# 4x_board.net
KiCad netlist of a schematic drawn in EAGLE
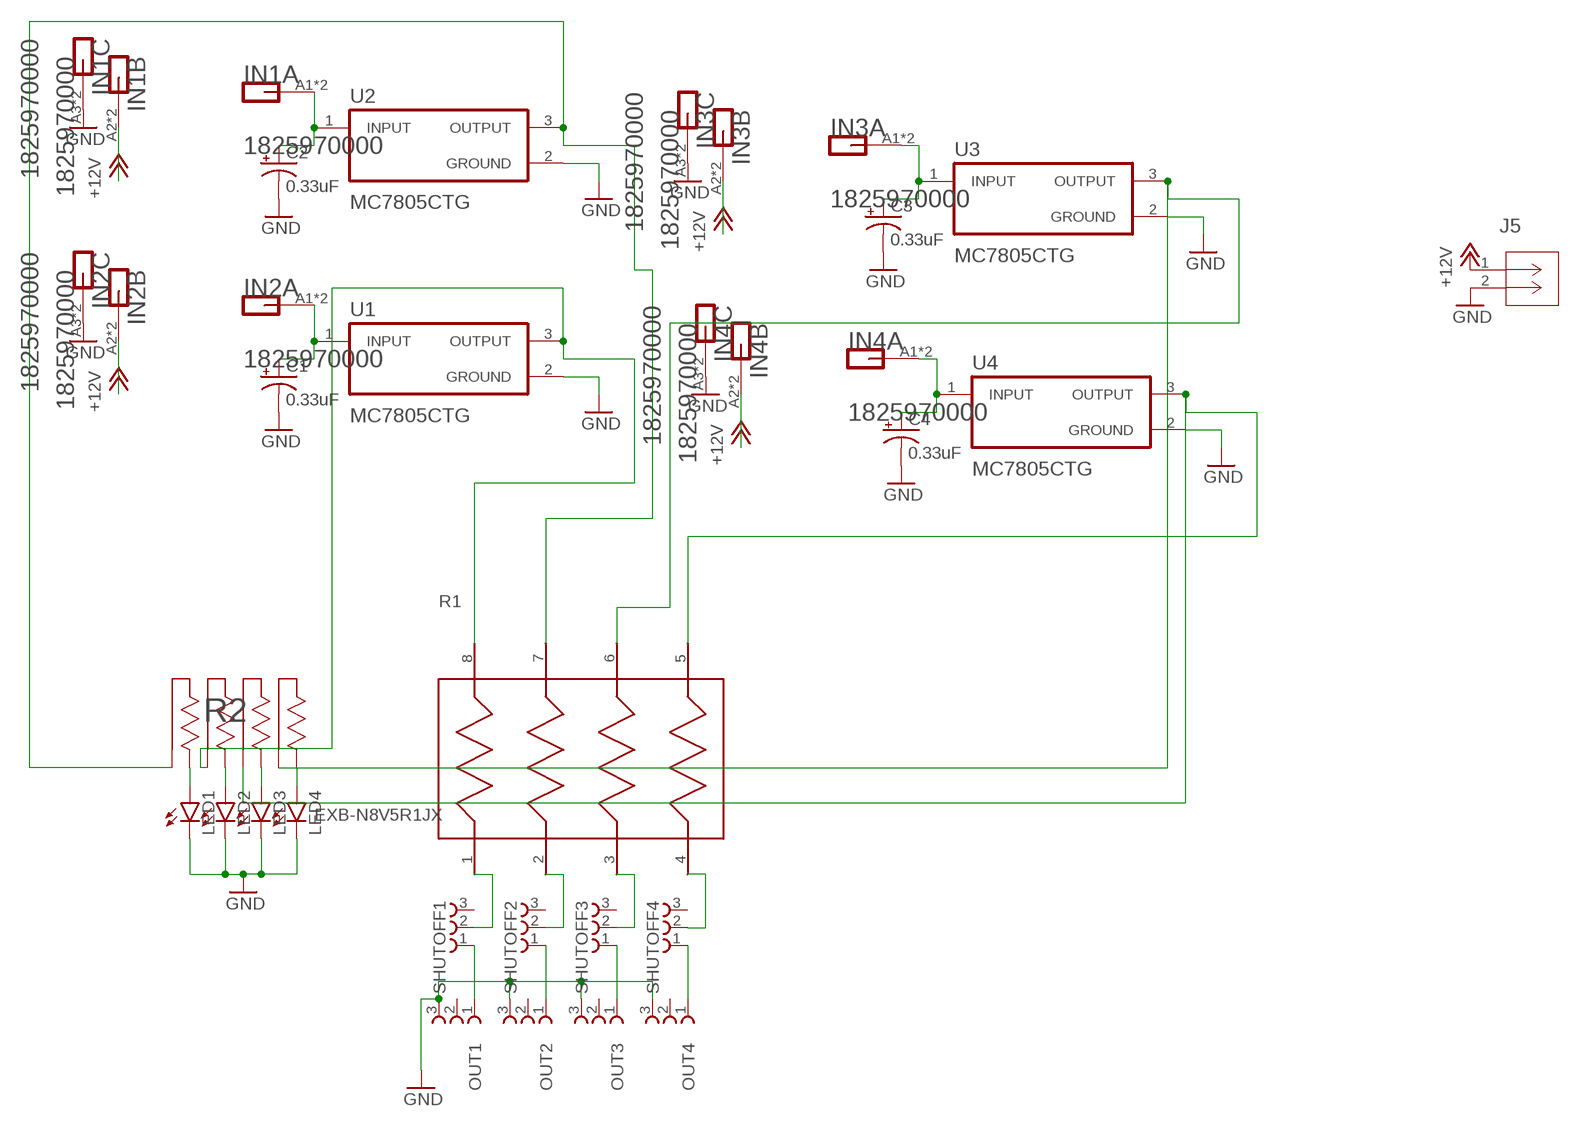
[diagram p0: schematic, sheet 1]

(export (version "E")
  (design (tool "Eeschema 10.0.6"))
  (components
    (comp (ref "C1")
      (value "0.33uF")
      (footprint "eagle-import:E2,5-5")
      (libsource (lib "eagle-import") (part "CPOL-USE2.5-5"))
    )
    (comp (ref "C2")
      (value "0.33uF")
      (footprint "eagle-import:E2,5-5")
      (libsource (lib "eagle-import") (part "CPOL-USE2.5-5"))
    )
    (comp (ref "C3")
      (value "0.33uF")
      (footprint "eagle-import:E2,5-5")
      (libsource (lib "eagle-import") (part "CPOL-USE2.5-5"))
    )
    (comp (ref "C4")
      (value "0.33uF")
      (footprint "eagle-import:E2,5-5")
      (libsource (lib "eagle-import") (part "CPOL-USE2.5-5"))
    )
    (comp (ref "IN1")
      (value "WEIDMUELLER_1825970000WEIDMUELLER_1825970000_0_0")
      (footprint "eagle-import:WEIDMUELLER_1825970000_0")
      (fields (field (name "MF") "Weidmueller") (field (name "MPN") "1825970000"))
      (libsource (lib "eagle-import") (part "WEIDMUELLER_1825970000WEIDMUELLER_1825970000_0_0"))
    )
    (comp (ref "IN2")
      (value "WEIDMUELLER_1825970000WEIDMUELLER_1825970000_0_0")
      (footprint "eagle-import:WEIDMUELLER_1825970000_0")
      (fields (field (name "MF") "Weidmueller") (field (name "MPN") "1825970000"))
      (libsource (lib "eagle-import") (part "WEIDMUELLER_1825970000WEIDMUELLER_1825970000_0_0"))
    )
    (comp (ref "IN3")
      (value "WEIDMUELLER_1825970000WEIDMUELLER_1825970000_0_0")
      (footprint "eagle-import:WEIDMUELLER_1825970000_0")
      (fields (field (name "MF") "Weidmueller") (field (name "MPN") "1825970000"))
      (libsource (lib "eagle-import") (part "WEIDMUELLER_1825970000WEIDMUELLER_1825970000_0_0"))
    )
    (comp (ref "IN4")
      (value "WEIDMUELLER_1825970000WEIDMUELLER_1825970000_0_0")
      (footprint "eagle-import:WEIDMUELLER_1825970000_0")
      (fields (field (name "MF") "Weidmueller") (field (name "MPN") "1825970000"))
      (libsource (lib "eagle-import") (part "WEIDMUELLER_1825970000WEIDMUELLER_1825970000_0_0"))
    )
    (comp (ref "J5")
      (value "2606-3102/020-000")
      (footprint "eagle-import:CONN3_2606-3102_020-000_WAG")
      (fields (field (name "COPYRIGHT") "Copyright (C) 2021 Ultra Librarian. All rights reserved."))
      (libsource (lib "eagle-import") (part "2606-3102/020-000"))
    )
    (comp (ref "LED1")
      (value "LED3MM")
      (footprint "eagle-import:LED3MM")
      (libsource (lib "eagle-import") (part "LED3MM"))
    )
    (comp (ref "LED2")
      (value "LED3MM")
      (footprint "eagle-import:LED3MM")
      (libsource (lib "eagle-import") (part "LED3MM"))
    )
    (comp (ref "LED3")
      (value "LED3MM")
      (footprint "eagle-import:LED3MM")
      (libsource (lib "eagle-import") (part "LED3MM"))
    )
    (comp (ref "LED4")
      (value "LED3MM")
      (footprint "eagle-import:LED3MM")
      (libsource (lib "eagle-import") (part "LED3MM"))
    )
    (comp (ref "OUT1")
      (value "61300311121")
      (footprint "eagle-import:61300311121")
      (fields (field (name "MF") "Würth Elektronik"))
      (libsource (lib "eagle-import") (part "61300311121"))
    )
    (comp (ref "OUT2")
      (value "61300311121")
      (footprint "eagle-import:61300311121")
      (fields (field (name "MF") "Würth Elektronik"))
      (libsource (lib "eagle-import") (part "61300311121"))
    )
    (comp (ref "OUT3")
      (value "61300311121")
      (footprint "eagle-import:61300311121")
      (fields (field (name "MF") "Würth Elektronik"))
      (libsource (lib "eagle-import") (part "61300311121"))
    )
    (comp (ref "OUT4")
      (value "61300311121")
      (footprint "eagle-import:61300311121")
      (fields (field (name "MF") "Würth Elektronik"))
      (libsource (lib "eagle-import") (part "61300311121"))
    )
    (comp (ref "R1")
      (value "EXB-N8V5R1JX")
      (footprint "eagle-import:RESCAV50P200X100X55-8N")
      (fields (field (name "DIGI-KEY_PART_NUMBER") "Y105R1CT-ND") (field (name "MF") "Panasonic"))
      (libsource (lib "eagle-import") (part "EXB-N8V5R1JX"))
    )
    (comp (ref "R2")
      (value "4608X-102-151LF")
      (footprint "eagle-import:BO_4608X")
      (fields (field (name "COPYRIGHT") "Copyright (C) 2021 Ultra Librarian. All rights reserved."))
      (libsource (lib "eagle-import") (part "4608X-102-151LF"))
    )
    (comp (ref "SHUTOFF1")
      (value "61300311121")
      (footprint "eagle-import:61300311121")
      (fields (field (name "MF") "Würth Elektronik"))
      (libsource (lib "eagle-import") (part "61300311121"))
    )
    (comp (ref "SHUTOFF2")
      (value "61300311121")
      (footprint "eagle-import:61300311121")
      (fields (field (name "MF") "Würth Elektronik"))
      (libsource (lib "eagle-import") (part "61300311121"))
    )
    (comp (ref "SHUTOFF3")
      (value "61300311121")
      (footprint "eagle-import:61300311121")
      (fields (field (name "MF") "Würth Elektronik"))
      (libsource (lib "eagle-import") (part "61300311121"))
    )
    (comp (ref "SHUTOFF4")
      (value "61300311121")
      (footprint "eagle-import:61300311121")
      (fields (field (name "MF") "Würth Elektronik"))
      (libsource (lib "eagle-import") (part "61300311121"))
    )
    (comp (ref "U1")
      (value "MC7805CTG")
      (footprint "eagle-import:TO254P1066X482X2286-3")
      (fields (field (name "MF") "ON Semiconductor"))
      (libsource (lib "eagle-import") (part "MC7805CTG"))
    )
    (comp (ref "U2")
      (value "MC7805CTG")
      (footprint "eagle-import:TO254P1066X482X2286-3")
      (fields (field (name "MF") "ON Semiconductor"))
      (libsource (lib "eagle-import") (part "MC7805CTG"))
    )
    (comp (ref "U3")
      (value "MC7805CTG")
      (footprint "eagle-import:TO254P1066X482X2286-3")
      (fields (field (name "MF") "ON Semiconductor"))
      (libsource (lib "eagle-import") (part "MC7805CTG"))
    )
    (comp (ref "U4")
      (value "MC7805CTG")
      (footprint "eagle-import:TO254P1066X482X2286-3")
      (fields (field (name "MF") "ON Semiconductor"))
      (libsource (lib "eagle-import") (part "MC7805CTG"))
    )
  )
  (nets
    (net (code "1") (name "+12V") (class "Default")
      (node (ref "IN1") (pin "A2") (pinfunction "A2_A2") (pintype "passive"))
      (node (ref "IN1") (pin "A2-2") (pinfunction "A2_A2-2") (pintype "passive"))
      (node (ref "IN2") (pin "A2") (pinfunction "A2_A2") (pintype "passive"))
      (node (ref "IN2") (pin "A2-2") (pinfunction "A2_A2-2") (pintype "passive"))
      (node (ref "IN3") (pin "A2") (pinfunction "A2_A2") (pintype "passive"))
      (node (ref "IN3") (pin "A2-2") (pinfunction "A2_A2-2") (pintype "passive"))
      (node (ref "IN4") (pin "A2") (pinfunction "A2_A2") (pintype "passive"))
      (node (ref "IN4") (pin "A2-2") (pinfunction "A2_A2-2") (pintype "passive"))
      (node (ref "J5") (pin "1") (pinfunction "1_1") (pintype "passive"))
    )
    (net (code "2") (name "GND") (class "Default")
      (node (ref "C1") (pin "-") (pinfunction "-_-") (pintype "passive"))
      (node (ref "C2") (pin "-") (pinfunction "-_-") (pintype "passive"))
      (node (ref "C3") (pin "-") (pinfunction "-_-") (pintype "passive"))
      (node (ref "C4") (pin "-") (pinfunction "-_-") (pintype "passive"))
      (node (ref "IN1") (pin "A3") (pinfunction "A3_A3") (pintype "passive"))
      (node (ref "IN1") (pin "A3-2") (pinfunction "A3_A3-2") (pintype "passive"))
      (node (ref "IN2") (pin "A3") (pinfunction "A3_A3") (pintype "passive"))
      (node (ref "IN2") (pin "A3-2") (pinfunction "A3_A3-2") (pintype "passive"))
      (node (ref "IN3") (pin "A3") (pinfunction "A3_A3") (pintype "passive"))
      (node (ref "IN3") (pin "A3-2") (pinfunction "A3_A3-2") (pintype "passive"))
      (node (ref "IN4") (pin "A3") (pinfunction "A3_A3") (pintype "passive"))
      (node (ref "IN4") (pin "A3-2") (pinfunction "A3_A3-2") (pintype "passive"))
      (node (ref "J5") (pin "2") (pinfunction "2_2") (pintype "passive"))
      (node (ref "LED1") (pin "K") (pinfunction "C_K") (pintype "passive"))
      (node (ref "LED2") (pin "K") (pinfunction "C_K") (pintype "passive"))
      (node (ref "LED3") (pin "K") (pinfunction "C_K") (pintype "passive"))
      (node (ref "LED4") (pin "K") (pinfunction "C_K") (pintype "passive"))
      (node (ref "OUT1") (pin "3") (pinfunction "3_3") (pintype "passive"))
      (node (ref "OUT2") (pin "3") (pinfunction "3_3") (pintype "passive"))
      (node (ref "OUT3") (pin "3") (pinfunction "3_3") (pintype "passive"))
      (node (ref "OUT4") (pin "3") (pinfunction "3_3") (pintype "passive"))
      (node (ref "U1") (pin "2") (pinfunction "GROUND_2") (pintype "power_in"))
      (node (ref "U2") (pin "2") (pinfunction "GROUND_2") (pintype "power_in"))
      (node (ref "U3") (pin "2") (pinfunction "GROUND_2") (pintype "power_in"))
      (node (ref "U4") (pin "2") (pinfunction "GROUND_2") (pintype "power_in"))
    )
    (net (code "3") (name "Net-(LED1-PadA)") (class "Default")
      (node (ref "LED1") (pin "A") (pinfunction "A_A") (pintype "passive"))
      (node (ref "R2") (pin "2") (pinfunction "2_2") (pintype "passive"))
    )
    (net (code "4") (name "Net-(LED2-PadA)") (class "Default")
      (node (ref "LED2") (pin "A") (pinfunction "A_A") (pintype "passive"))
      (node (ref "R2") (pin "4") (pinfunction "4_4") (pintype "passive"))
    )
    (net (code "5") (name "Net-(LED3-PadA)") (class "Default")
      (node (ref "LED3") (pin "A") (pinfunction "A_A") (pintype "passive"))
      (node (ref "R2") (pin "6") (pinfunction "6_6") (pintype "passive"))
    )
    (net (code "6") (name "Net-(LED4-PadA)") (class "Default")
      (node (ref "LED4") (pin "A") (pinfunction "A_A") (pintype "passive"))
      (node (ref "R2") (pin "8") (pinfunction "8_8") (pintype "passive"))
    )
    (net (code "7") (name "Net-(OUT1-Pad1)") (class "Default")
      (node (ref "OUT1") (pin "1") (pinfunction "1_1") (pintype "passive"))
      (node (ref "SHUTOFF1") (pin "1") (pinfunction "1_1") (pintype "passive"))
    )
    (net (code "8") (name "Net-(OUT2-Pad1)") (class "Default")
      (node (ref "OUT2") (pin "1") (pinfunction "1_1") (pintype "passive"))
      (node (ref "SHUTOFF2") (pin "1") (pinfunction "1_1") (pintype "passive"))
    )
    (net (code "9") (name "Net-(OUT3-Pad1)") (class "Default")
      (node (ref "OUT3") (pin "1") (pinfunction "1_1") (pintype "passive"))
      (node (ref "SHUTOFF3") (pin "1") (pinfunction "1_1") (pintype "passive"))
    )
    (net (code "10") (name "Net-(OUT4-Pad1)") (class "Default")
      (node (ref "OUT4") (pin "1") (pinfunction "1_1") (pintype "passive"))
      (node (ref "SHUTOFF4") (pin "1") (pinfunction "1_1") (pintype "passive"))
    )
    (net (code "11") (name "Net-(R1-Pad1)") (class "Default")
      (node (ref "R1") (pin "1") (pinfunction "1_1") (pintype "passive"))
      (node (ref "SHUTOFF1") (pin "2") (pinfunction "2_2") (pintype "passive"))
    )
    (net (code "12") (name "Net-(R1-Pad2)") (class "Default")
      (node (ref "R1") (pin "2") (pinfunction "2_2") (pintype "passive"))
      (node (ref "SHUTOFF2") (pin "2") (pinfunction "2_2") (pintype "passive"))
    )
    (net (code "13") (name "Net-(R1-Pad3)") (class "Default")
      (node (ref "R1") (pin "3") (pinfunction "3_3") (pintype "passive"))
      (node (ref "SHUTOFF3") (pin "2") (pinfunction "2_2") (pintype "passive"))
    )
    (net (code "14") (name "Net-(R1-Pad4)") (class "Default")
      (node (ref "R1") (pin "4") (pinfunction "4_4") (pintype "passive"))
      (node (ref "SHUTOFF4") (pin "2") (pinfunction "2_2") (pintype "passive"))
    )
    (net (code "15") (name "Net-(U1-INPUT)") (class "Default")
      (node (ref "C1") (pin "+") (pinfunction "+_+") (pintype "passive"))
      (node (ref "IN2") (pin "A1") (pinfunction "A1_A1") (pintype "passive"))
      (node (ref "IN2") (pin "A1-2") (pinfunction "A1_A1-2") (pintype "passive"))
      (node (ref "U1") (pin "1") (pinfunction "INPUT_1") (pintype "input"))
    )
    (net (code "16") (name "Net-(U1-OUTPUT)") (class "Default")
      (node (ref "R1") (pin "8") (pinfunction "8_8") (pintype "passive"))
      (node (ref "R2") (pin "3") (pinfunction "3_3") (pintype "passive"))
      (node (ref "U1") (pin "3") (pinfunction "OUTPUT_3") (pintype "output"))
    )
    (net (code "17") (name "Net-(U2-INPUT)") (class "Default")
      (node (ref "C2") (pin "+") (pinfunction "+_+") (pintype "passive"))
      (node (ref "IN1") (pin "A1") (pinfunction "A1_A1") (pintype "passive"))
      (node (ref "IN1") (pin "A1-2") (pinfunction "A1_A1-2") (pintype "passive"))
      (node (ref "U2") (pin "1") (pinfunction "INPUT_1") (pintype "input"))
    )
    (net (code "18") (name "Net-(U2-OUTPUT)") (class "Default")
      (node (ref "R1") (pin "7") (pinfunction "7_7") (pintype "passive"))
      (node (ref "R2") (pin "1") (pinfunction "1_1") (pintype "passive"))
      (node (ref "U2") (pin "3") (pinfunction "OUTPUT_3") (pintype "output"))
    )
    (net (code "19") (name "Net-(U3-INPUT)") (class "Default")
      (node (ref "C3") (pin "+") (pinfunction "+_+") (pintype "passive"))
      (node (ref "IN3") (pin "A1") (pinfunction "A1_A1") (pintype "passive"))
      (node (ref "IN3") (pin "A1-2") (pinfunction "A1_A1-2") (pintype "passive"))
      (node (ref "U3") (pin "1") (pinfunction "INPUT_1") (pintype "input"))
    )
    (net (code "20") (name "Net-(U3-OUTPUT)") (class "Default")
      (node (ref "R1") (pin "6") (pinfunction "6_6") (pintype "passive"))
      (node (ref "R2") (pin "7") (pinfunction "7_7") (pintype "passive"))
      (node (ref "U3") (pin "3") (pinfunction "OUTPUT_3") (pintype "output"))
    )
    (net (code "21") (name "Net-(U4-INPUT)") (class "Default")
      (node (ref "C4") (pin "+") (pinfunction "+_+") (pintype "passive"))
      (node (ref "IN4") (pin "A1") (pinfunction "A1_A1") (pintype "passive"))
      (node (ref "IN4") (pin "A1-2") (pinfunction "A1_A1-2") (pintype "passive"))
      (node (ref "U4") (pin "1") (pinfunction "INPUT_1") (pintype "input"))
    )
    (net (code "22") (name "Net-(U4-OUTPUT)") (class "Default")
      (node (ref "R1") (pin "5") (pinfunction "5_5") (pintype "passive"))
      (node (ref "R2") (pin "5") (pinfunction "5_5") (pintype "passive"))
      (node (ref "U4") (pin "3") (pinfunction "OUTPUT_3") (pintype "output"))
    )
    (net (code "23") (name "unconnected-(OUT1-Pad2)") (class "Default")
      (node (ref "OUT1") (pin "2") (pinfunction "2_2") (pintype "passive"))
    )
    (net (code "24") (name "unconnected-(OUT2-Pad2)") (class "Default")
      (node (ref "OUT2") (pin "2") (pinfunction "2_2") (pintype "passive"))
    )
    (net (code "25") (name "unconnected-(OUT3-Pad2)") (class "Default")
      (node (ref "OUT3") (pin "2") (pinfunction "2_2") (pintype "passive"))
    )
    (net (code "26") (name "unconnected-(OUT4-Pad2)") (class "Default")
      (node (ref "OUT4") (pin "2") (pinfunction "2_2") (pintype "passive"))
    )
    (net (code "27") (name "unconnected-(SHUTOFF1-Pad3)") (class "Default")
      (node (ref "SHUTOFF1") (pin "3") (pinfunction "3_3") (pintype "passive"))
    )
    (net (code "28") (name "unconnected-(SHUTOFF2-Pad3)") (class "Default")
      (node (ref "SHUTOFF2") (pin "3") (pinfunction "3_3") (pintype "passive"))
    )
    (net (code "29") (name "unconnected-(SHUTOFF3-Pad3)") (class "Default")
      (node (ref "SHUTOFF3") (pin "3") (pinfunction "3_3") (pintype "passive"))
    )
    (net (code "30") (name "unconnected-(SHUTOFF4-Pad3)") (class "Default")
      (node (ref "SHUTOFF4") (pin "3") (pinfunction "3_3") (pintype "passive"))
    )
  )
)
